# usb.net
KiCad netlist of a schematic drawn in Altium Designer
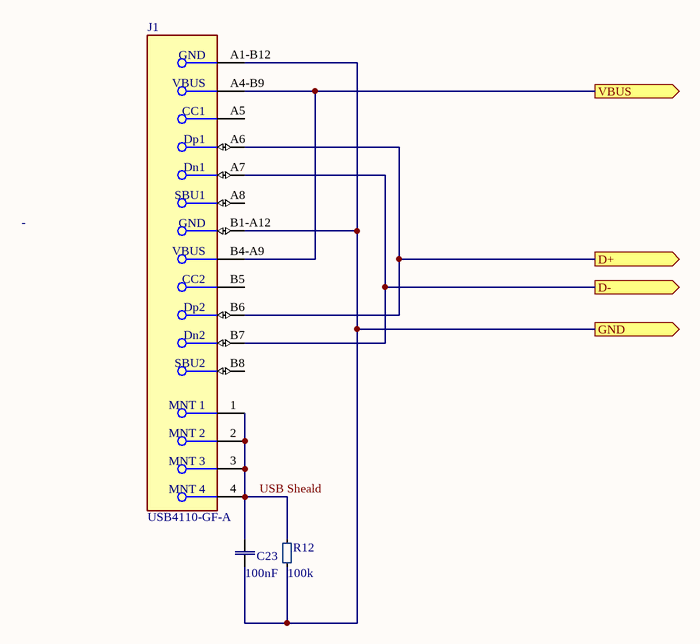
[diagram p0: usb.SchDoc]

(export (version "E")
  (design (tool "Eeschema 10.0.6"))
  (components
    (comp (ref "C23")
      (value "GRM155R71H104ME14D")
      (footprint "cap0402")
      (description "0402 0.1 uF 50 V ±20% Tolerance X7R SMT Monolithic Ceramic Chip Capacitor")
      (fields
        (field (name "CAPACITANCE") "100nF")
        (field (name "TOLERANCE") "20%")
        (field (name "LCSC PART#") "C182412")
      )
      (libsource (lib "concord server") (part "Capasitor_keramic_generic"))
    )
    (comp (ref "J1")
      (value "USB4110-GF-A")
      (footprint "FP-USB4110-GF-A-MFG")
      (description "Conn Usb 2.0 Type-c R/a SMT")
      (libsource (lib "concord server") (part "e23f2b38bb3c3f98e683ebab9ede730"))
    )
    (comp (ref "R12")
      (value "RC0402FR-07100KL")
      (footprint "SMD_0402(1005)_M")
      (description "Res General Purpose Thick Film 0402 100K Ohm 1% 1/16W ±100ppm/°C Molded SMD Paper T/R")
      (fields
        (field (name "RESISTANCE") "100k")
        (field (name "TOLERANCE") "1%")
        (field (name "LCSC PART#") "C60491")
      )
      (libsource (lib "concord server") (part "resistor_european"))
    )
  )
  (nets
    (net (code "1") (name "/D+") (class "Default")
      (node (ref "J1") (pin "A6") (pinfunction "Dp1_A6") (pintype "bidirectional"))
      (node (ref "J1") (pin "B6") (pinfunction "Dp2_B6") (pintype "bidirectional"))
    )
    (net (code "2") (name "/D-") (class "Default")
      (node (ref "J1") (pin "A7") (pinfunction "Dn1_A7") (pintype "bidirectional"))
      (node (ref "J1") (pin "B7") (pinfunction "Dn2_B7") (pintype "bidirectional"))
    )
    (net (code "3") (name "/GND") (class "Default")
      (node (ref "C23") (pin "1") (pinfunction "1_1") (pintype "passive"))
      (node (ref "J1") (pin "A1-B12") (pinfunction "GND_A1-B12") (pintype "passive"))
      (node (ref "J1") (pin "B1-A12") (pinfunction "GND_B1-A12") (pintype "bidirectional"))
      (node (ref "R12") (pin "1") (pinfunction "1_1") (pintype "passive"))
    )
    (net (code "4") (name "/USB Sheald") (class "Default")
      (node (ref "C23") (pin "2") (pinfunction "2_2") (pintype "passive"))
      (node (ref "J1") (pin "1") (pinfunction "MNT_1_1") (pintype "passive"))
      (node (ref "J1") (pin "2") (pinfunction "MNT_2_2") (pintype "passive"))
      (node (ref "J1") (pin "3") (pinfunction "MNT_3_3") (pintype "passive"))
      (node (ref "J1") (pin "4") (pinfunction "MNT_4_4") (pintype "passive"))
      (node (ref "R12") (pin "2") (pinfunction "2_2") (pintype "passive"))
    )
    (net (code "5") (name "/VBUS") (class "Default")
      (node (ref "J1") (pin "A4-B9") (pinfunction "VBUS_A4-B9") (pintype "power_in"))
      (node (ref "J1") (pin "B4-A9") (pinfunction "VBUS_B4-A9") (pintype "power_in"))
    )
    (net (code "6") (name "unconnected-(J1-CC1-PadA5)") (class "Default")
      (node (ref "J1") (pin "A5") (pinfunction "CC1_A5") (pintype "power_in"))
    )
    (net (code "7") (name "unconnected-(J1-CC2-PadB5)") (class "Default")
      (node (ref "J1") (pin "B5") (pinfunction "CC2_B5") (pintype "power_in"))
    )
    (net (code "8") (name "unconnected-(J1-SBU1-PadA8)") (class "Default")
      (node (ref "J1") (pin "A8") (pinfunction "SBU1_A8") (pintype "bidirectional"))
    )
    (net (code "9") (name "unconnected-(J1-SBU2-PadB8)") (class "Default")
      (node (ref "J1") (pin "B8") (pinfunction "SBU2_B8") (pintype "bidirectional"))
    )
  )
)
